# project_1.net
KiCad netlist of a schematic drawn in Altium Designer
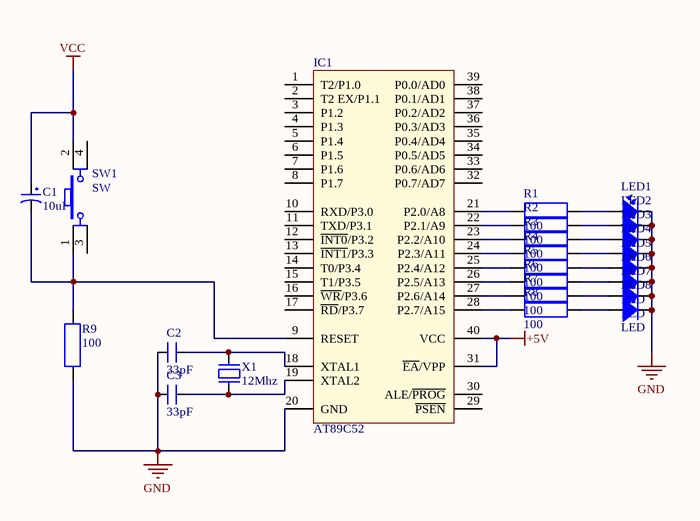
[diagram p0: project_1.SchDoc]

(export (version "E")
  (design (tool "Eeschema 10.0.6"))
  (components
    (comp (ref "C1")
      (value "10uF")
      (footprint "CP1/2")
      (description "Cap P  0,1uF < 22uF , 16 - 50V")
      (libsource (lib "syhaunguyen") (part "CP1"))
    )
    (comp (ref "C2")
      (value "33pF")
      (footprint "CN1.5")
      (description "Cap np 682pF => 104pF")
      (libsource (lib "syhaunguyen") (part "CN1.5"))
    )
    (comp (ref "C3")
      (value "33pF")
      (footprint "CN1.5")
      (description "Cap np 682pF => 104pF")
      (libsource (lib "syhaunguyen") (part "CN1.5"))
    )
    (comp (ref "IC1")
      (value "AT89C52")
      (footprint "DIP40/W0.6")
      (description "Atmel AT89C52, 8k Byte Flash Memory , 40 Pin")
      (libsource (lib "syhaunguyen") (part "AT89C52"))
    )
    (comp (ref "LED1")
      (value "LED")
      (footprint "LED-3")
      (description "LED Single colour Green and Red")
      (libsource (lib "syhaunguyen") (part "LED"))
    )
    (comp (ref "LED2")
      (value "LED")
      (footprint "LED-3")
      (description "LED Single colour Green and Red")
      (libsource (lib "syhaunguyen") (part "LED"))
    )
    (comp (ref "LED3")
      (value "LED")
      (footprint "LED-3")
      (description "LED Single colour Green and Red")
      (libsource (lib "syhaunguyen") (part "LED"))
    )
    (comp (ref "LED4")
      (value "LED")
      (footprint "LED-3")
      (description "LED Single colour Green and Red")
      (libsource (lib "syhaunguyen") (part "LED"))
    )
    (comp (ref "LED5")
      (value "LED")
      (footprint "LED-3")
      (description "LED Single colour Green and Red")
      (libsource (lib "syhaunguyen") (part "LED"))
    )
    (comp (ref "LED6")
      (value "LED")
      (footprint "LED-3")
      (description "LED Single colour Green and Red")
      (libsource (lib "syhaunguyen") (part "LED"))
    )
    (comp (ref "LED7")
      (value "LED")
      (footprint "LED-3")
      (description "LED Single colour Green and Red")
      (libsource (lib "syhaunguyen") (part "LED"))
    )
    (comp (ref "LED8")
      (value "LED")
      (footprint "LED-3")
      (description "LED Single colour Green and Red")
      (libsource (lib "syhaunguyen") (part "LED"))
    )
    (comp (ref "R1")
      (value "100")
      (footprint "R1W")
      (description "Resistor 1W")
      (libsource (lib "syhaunguyen") (part "R1W"))
    )
    (comp (ref "R2")
      (value "100")
      (footprint "R1W")
      (description "Resistor 1W")
      (libsource (lib "syhaunguyen") (part "R1W"))
    )
    (comp (ref "R3")
      (value "100")
      (footprint "R1W")
      (description "Resistor 1W")
      (libsource (lib "syhaunguyen") (part "R1W"))
    )
    (comp (ref "R4")
      (value "100")
      (footprint "R1W")
      (description "Resistor 1W")
      (libsource (lib "syhaunguyen") (part "R1W"))
    )
    (comp (ref "R5")
      (value "100")
      (footprint "R1W")
      (description "Resistor 1W")
      (libsource (lib "syhaunguyen") (part "R1W"))
    )
    (comp (ref "R6")
      (value "100")
      (footprint "R1W")
      (description "Resistor 1W")
      (libsource (lib "syhaunguyen") (part "R1W"))
    )
    (comp (ref "R7")
      (value "100")
      (footprint "R1W")
      (description "Resistor 1W")
      (libsource (lib "syhaunguyen") (part "R1W"))
    )
    (comp (ref "R8")
      (value "100")
      (footprint "R1W")
      (description "Resistor 1W")
      (libsource (lib "syhaunguyen") (part "R1W"))
    )
    (comp (ref "R9")
      (value "100")
      (footprint "R1W")
      (description "Resistor 1W")
      (libsource (lib "syhaunguyen") (part "R1W"))
    )
    (comp (ref "SW1")
      (value "SW")
      (footprint "SW4")
      (description "Switch button 4 pin")
      (libsource (lib "syhaunguyen") (part "SW4"))
    )
    (comp (ref "X1")
      (value "12Mhz")
      (footprint "XT32k")
      (description "Crystal 32,768kHz for timer real")
      (libsource (lib "syhaunguyen") (part "XT32k"))
    )
  )
  (nets
    (net (code "1") (name "+5V") (class "Default")
      (node (ref "IC1") (pin "31") (pinfunction "~{EA}/VPP_31") (pintype "passive"))
      (node (ref "IC1") (pin "40") (pinfunction "VCC_40") (pintype "power_in"))
    )
    (net (code "2") (name "GND") (class "Default")
      (node (ref "C2") (pin "1") (pinfunction "1_1") (pintype "passive"))
      (node (ref "C3") (pin "1") (pinfunction "1_1") (pintype "passive"))
      (node (ref "IC1") (pin "20") (pinfunction "GND_20") (pintype "open_emitter"))
      (node (ref "LED1") (pin "2") (pinfunction "2_2") (pintype "passive"))
      (node (ref "LED2") (pin "2") (pinfunction "2_2") (pintype "passive"))
      (node (ref "LED3") (pin "2") (pinfunction "2_2") (pintype "passive"))
      (node (ref "LED4") (pin "2") (pinfunction "2_2") (pintype "passive"))
      (node (ref "LED5") (pin "2") (pinfunction "2_2") (pintype "passive"))
      (node (ref "LED6") (pin "2") (pinfunction "2_2") (pintype "passive"))
      (node (ref "LED7") (pin "2") (pinfunction "2_2") (pintype "passive"))
      (node (ref "LED8") (pin "2") (pinfunction "2_2") (pintype "passive"))
      (node (ref "R9") (pin "1") (pinfunction "1_1") (pintype "passive"))
    )
    (net (code "3") (name "Net-(IC1-P2.0{slash}A8)") (class "Default")
      (node (ref "IC1") (pin "21") (pinfunction "P2.0/A8_21") (pintype "passive"))
      (node (ref "R1") (pin "1") (pinfunction "1_1") (pintype "passive"))
    )
    (net (code "4") (name "Net-(IC1-P2.1{slash}A9)") (class "Default")
      (node (ref "IC1") (pin "22") (pinfunction "P2.1/A9_22") (pintype "passive"))
      (node (ref "R2") (pin "1") (pinfunction "1_1") (pintype "passive"))
    )
    (net (code "5") (name "Net-(IC1-P2.2{slash}A10)") (class "Default")
      (node (ref "IC1") (pin "23") (pinfunction "P2.2/A10_23") (pintype "passive"))
      (node (ref "R3") (pin "1") (pinfunction "1_1") (pintype "passive"))
    )
    (net (code "6") (name "Net-(IC1-P2.3{slash}A11)") (class "Default")
      (node (ref "IC1") (pin "24") (pinfunction "P2.3/A11_24") (pintype "passive"))
      (node (ref "R4") (pin "1") (pinfunction "1_1") (pintype "passive"))
    )
    (net (code "7") (name "Net-(IC1-P2.4{slash}A12)") (class "Default")
      (node (ref "IC1") (pin "25") (pinfunction "P2.4/A12_25") (pintype "passive"))
      (node (ref "R5") (pin "1") (pinfunction "1_1") (pintype "passive"))
    )
    (net (code "8") (name "Net-(IC1-P2.5{slash}A13)") (class "Default")
      (node (ref "IC1") (pin "26") (pinfunction "P2.5/A13_26") (pintype "passive"))
      (node (ref "R6") (pin "1") (pinfunction "1_1") (pintype "passive"))
    )
    (net (code "9") (name "Net-(IC1-P2.6{slash}A14)") (class "Default")
      (node (ref "IC1") (pin "27") (pinfunction "P2.6/A14_27") (pintype "passive"))
      (node (ref "R7") (pin "1") (pinfunction "1_1") (pintype "passive"))
    )
    (net (code "10") (name "Net-(IC1-P2.7{slash}A15)") (class "Default")
      (node (ref "IC1") (pin "28") (pinfunction "P2.7/A15_28") (pintype "passive"))
      (node (ref "R8") (pin "1") (pinfunction "1_1") (pintype "passive"))
    )
    (net (code "11") (name "Net-(IC1-RESET)") (class "Default")
      (node (ref "C1") (pin "2") (pinfunction "2_2") (pintype "passive"))
      (node (ref "IC1") (pin "9") (pinfunction "RESET_9") (pintype "passive"))
      (node (ref "R9") (pin "2") (pinfunction "2_2") (pintype "passive"))
      (node (ref "SW1") (pin "1") (pintype "passive"))
    )
    (net (code "12") (name "Net-(IC1-XTAL1)") (class "Default")
      (node (ref "C2") (pin "2") (pinfunction "2_2") (pintype "passive"))
      (node (ref "IC1") (pin "18") (pinfunction "XTAL1_18") (pintype "passive"))
      (node (ref "X1") (pin "2") (pinfunction "2_2") (pintype "passive"))
    )
    (net (code "13") (name "Net-(IC1-XTAL2)") (class "Default")
      (node (ref "C3") (pin "2") (pinfunction "2_2") (pintype "passive"))
      (node (ref "IC1") (pin "19") (pinfunction "XTAL2_19") (pintype "passive"))
      (node (ref "X1") (pin "1") (pinfunction "1_1") (pintype "passive"))
    )
    (net (code "14") (name "Net-(LED1-Pad1)") (class "Default")
      (node (ref "LED1") (pin "1") (pinfunction "1_1") (pintype "passive"))
      (node (ref "R1") (pin "2") (pinfunction "2_2") (pintype "passive"))
    )
    (net (code "15") (name "Net-(LED2-Pad1)") (class "Default")
      (node (ref "LED2") (pin "1") (pinfunction "1_1") (pintype "passive"))
      (node (ref "R2") (pin "2") (pinfunction "2_2") (pintype "passive"))
    )
    (net (code "16") (name "Net-(LED3-Pad1)") (class "Default")
      (node (ref "LED3") (pin "1") (pinfunction "1_1") (pintype "passive"))
      (node (ref "R3") (pin "2") (pinfunction "2_2") (pintype "passive"))
    )
    (net (code "17") (name "Net-(LED4-Pad1)") (class "Default")
      (node (ref "LED4") (pin "1") (pinfunction "1_1") (pintype "passive"))
      (node (ref "R4") (pin "2") (pinfunction "2_2") (pintype "passive"))
    )
    (net (code "18") (name "Net-(LED5-Pad1)") (class "Default")
      (node (ref "LED5") (pin "1") (pinfunction "1_1") (pintype "passive"))
      (node (ref "R5") (pin "2") (pinfunction "2_2") (pintype "passive"))
    )
    (net (code "19") (name "Net-(LED6-Pad1)") (class "Default")
      (node (ref "LED6") (pin "1") (pinfunction "1_1") (pintype "passive"))
      (node (ref "R6") (pin "2") (pinfunction "2_2") (pintype "passive"))
    )
    (net (code "20") (name "Net-(LED7-Pad1)") (class "Default")
      (node (ref "LED7") (pin "1") (pinfunction "1_1") (pintype "passive"))
      (node (ref "R7") (pin "2") (pinfunction "2_2") (pintype "passive"))
    )
    (net (code "21") (name "Net-(LED8-Pad1)") (class "Default")
      (node (ref "LED8") (pin "1") (pinfunction "1_1") (pintype "passive"))
      (node (ref "R8") (pin "2") (pinfunction "2_2") (pintype "passive"))
    )
    (net (code "22") (name "VCC") (class "Default")
      (node (ref "C1") (pin "1") (pinfunction "1_1") (pintype "passive"))
      (node (ref "SW1") (pin "2") (pintype "passive"))
    )
    (net (code "23") (name "unconnected-(IC1-ALE{slash}~{PROG}-Pad30)") (class "Default")
      (node (ref "IC1") (pin "30") (pinfunction "ALE/~{PROG}_30") (pintype "passive"))
    )
    (net (code "24") (name "unconnected-(IC1-P0.0{slash}AD0-Pad39)") (class "Default")
      (node (ref "IC1") (pin "39") (pinfunction "P0.0/AD0_39") (pintype "passive"))
    )
    (net (code "25") (name "unconnected-(IC1-P0.1{slash}AD1-Pad38)") (class "Default")
      (node (ref "IC1") (pin "38") (pinfunction "P0.1/AD1_38") (pintype "passive"))
    )
    (net (code "26") (name "unconnected-(IC1-P0.2{slash}AD2-Pad37)") (class "Default")
      (node (ref "IC1") (pin "37") (pinfunction "P0.2/AD2_37") (pintype "passive"))
    )
    (net (code "27") (name "unconnected-(IC1-P0.3{slash}AD3-Pad36)") (class "Default")
      (node (ref "IC1") (pin "36") (pinfunction "P0.3/AD3_36") (pintype "passive"))
    )
    (net (code "28") (name "unconnected-(IC1-P0.4{slash}AD4-Pad35)") (class "Default")
      (node (ref "IC1") (pin "35") (pinfunction "P0.4/AD4_35") (pintype "passive"))
    )
    (net (code "29") (name "unconnected-(IC1-P0.5{slash}AD5-Pad34)") (class "Default")
      (node (ref "IC1") (pin "34") (pinfunction "P0.5/AD5_34") (pintype "passive"))
    )
    (net (code "30") (name "unconnected-(IC1-P0.6{slash}AD6-Pad33)") (class "Default")
      (node (ref "IC1") (pin "33") (pinfunction "P0.6/AD6_33") (pintype "passive"))
    )
    (net (code "31") (name "unconnected-(IC1-P0.7{slash}AD7-Pad32)") (class "Default")
      (node (ref "IC1") (pin "32") (pinfunction "P0.7/AD7_32") (pintype "passive"))
    )
    (net (code "32") (name "unconnected-(IC1-P1.2-Pad3)") (class "Default")
      (node (ref "IC1") (pin "3") (pinfunction "P1.2_3") (pintype "passive"))
    )
    (net (code "33") (name "unconnected-(IC1-P1.3-Pad4)") (class "Default")
      (node (ref "IC1") (pin "4") (pinfunction "P1.3_4") (pintype "passive"))
    )
    (net (code "34") (name "unconnected-(IC1-P1.4-Pad5)") (class "Default")
      (node (ref "IC1") (pin "5") (pinfunction "P1.4_5") (pintype "passive"))
    )
    (net (code "35") (name "unconnected-(IC1-P1.5-Pad6)") (class "Default")
      (node (ref "IC1") (pin "6") (pinfunction "P1.5_6") (pintype "passive"))
    )
    (net (code "36") (name "unconnected-(IC1-P1.6-Pad7)") (class "Default")
      (node (ref "IC1") (pin "7") (pinfunction "P1.6_7") (pintype "passive"))
    )
    (net (code "37") (name "unconnected-(IC1-P1.7-Pad8)") (class "Default")
      (node (ref "IC1") (pin "8") (pinfunction "P1.7_8") (pintype "passive"))
    )
    (net (code "38") (name "unconnected-(IC1-RXD{slash}P3.0-Pad10)") (class "Default")
      (node (ref "IC1") (pin "10") (pinfunction "RXD/P3.0_10") (pintype "passive"))
    )
    (net (code "39") (name "unconnected-(IC1-T0{slash}P3.4-Pad14)") (class "Default")
      (node (ref "IC1") (pin "14") (pinfunction "T0/P3.4_14") (pintype "passive"))
    )
    (net (code "40") (name "unconnected-(IC1-T1{slash}P3.5-Pad15)") (class "Default")
      (node (ref "IC1") (pin "15") (pinfunction "T1/P3.5_15") (pintype "passive"))
    )
    (net (code "41") (name "unconnected-(IC1-T2_EX{slash}P1.1-Pad2)") (class "Default")
      (node (ref "IC1") (pin "2") (pinfunction "T2_EX/P1.1_2") (pintype "passive"))
    )
    (net (code "42") (name "unconnected-(IC1-T2{slash}P1.0-Pad1)") (class "Default")
      (node (ref "IC1") (pin "1") (pinfunction "T2/P1.0_1") (pintype "passive"))
    )
    (net (code "43") (name "unconnected-(IC1-TXD{slash}P3.1-Pad11)") (class "Default")
      (node (ref "IC1") (pin "11") (pinfunction "TXD/P3.1_11") (pintype "passive"))
    )
    (net (code "44") (name "unconnected-(IC1-~{INT0}{slash}P3.2-Pad12)") (class "Default")
      (node (ref "IC1") (pin "12") (pinfunction "~{INT0}/P3.2_12") (pintype "passive"))
    )
    (net (code "45") (name "unconnected-(IC1-~{INT1}{slash}P3.3-Pad13)") (class "Default")
      (node (ref "IC1") (pin "13") (pinfunction "~{INT1}/P3.3_13") (pintype "passive"))
    )
    (net (code "46") (name "unconnected-(IC1-~{PSEN}-Pad29)") (class "Default")
      (node (ref "IC1") (pin "29") (pinfunction "~{PSEN}_29") (pintype "passive"))
    )
    (net (code "47") (name "unconnected-(IC1-~{RD}{slash}P3.7-Pad17)") (class "Default")
      (node (ref "IC1") (pin "17") (pinfunction "~{RD}/P3.7_17") (pintype "passive"))
    )
    (net (code "48") (name "unconnected-(IC1-~{WR}{slash}P3.6-Pad16)") (class "Default")
      (node (ref "IC1") (pin "16") (pinfunction "~{WR}/P3.6_16") (pintype "passive"))
    )
    (net (code "49") (name "unconnected-(SW1-Pad3)") (class "Default")
      (node (ref "SW1") (pin "3") (pintype "passive"))
    )
    (net (code "50") (name "unconnected-(SW1-Pad4)") (class "Default")
      (node (ref "SW1") (pin "4") (pintype "passive"))
    )
  )
)
